# Charging.net
KiCad netlist of a schematic drawn in Altium Designer
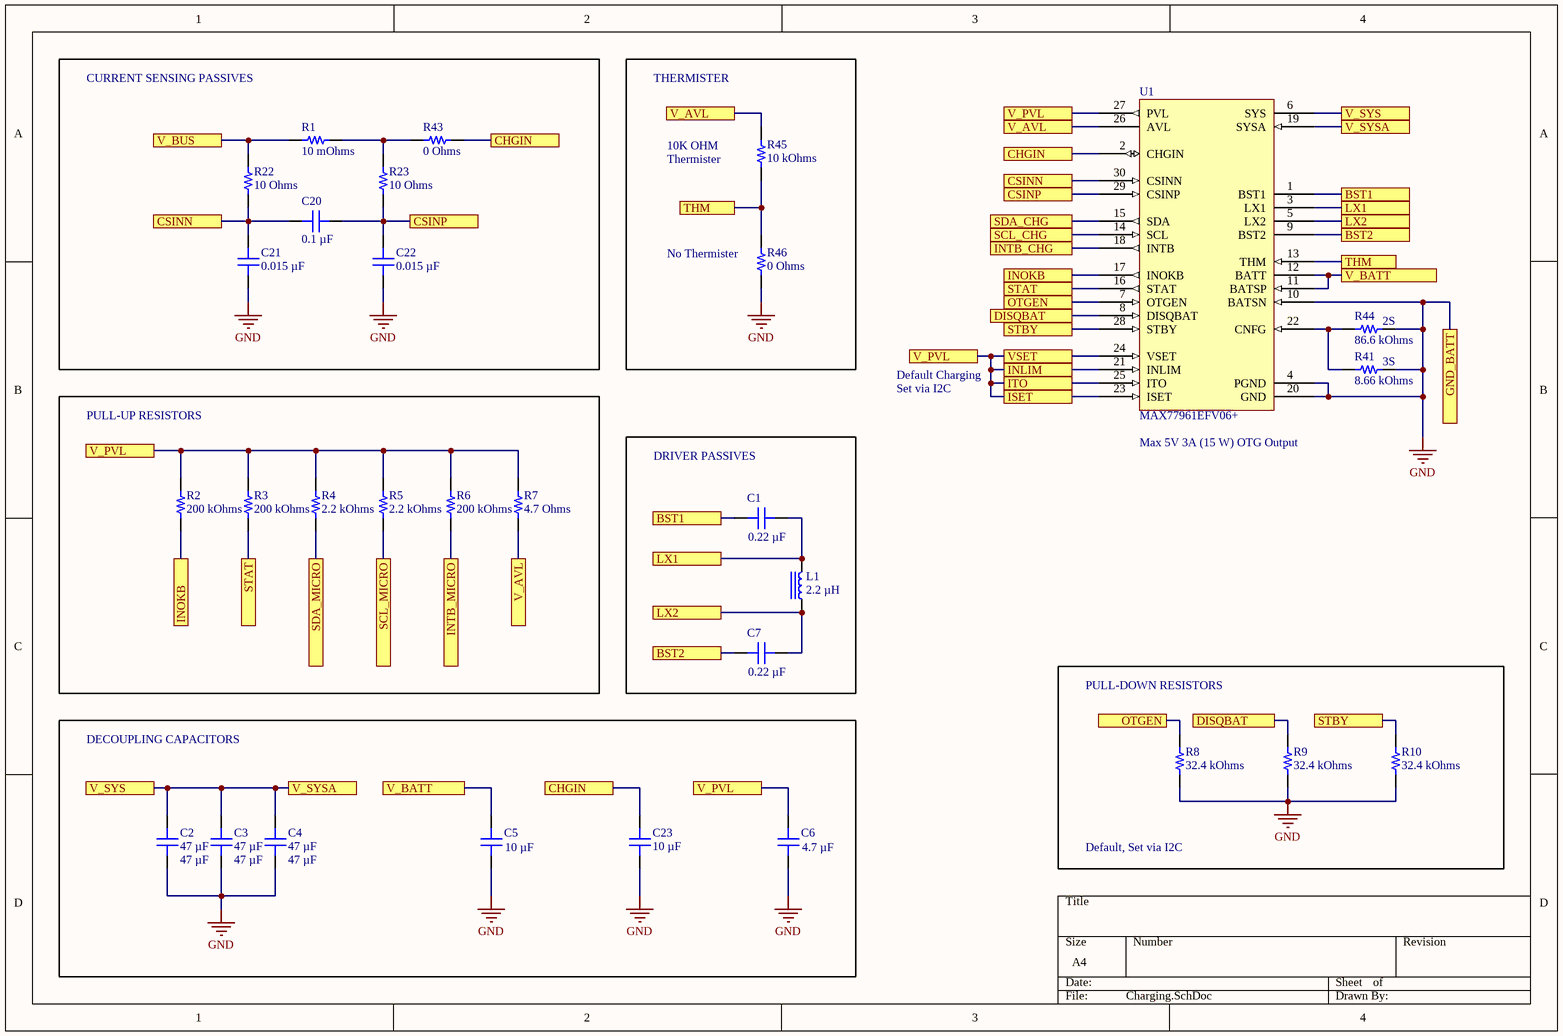
[diagram p0: Charging.SchDoc]

(export (version "E")
  (design (tool "Eeschema 10.0.6"))
  (components
    (comp (ref "C1")
      (value "0.22 µF")
      (footprint "CAP 0402_1005")
      (description "CAP CER 0.22UF 6.3V X7R 0402")
      (fields (field (name "PART NUMBER") "JMK105B7224KV-F") (field (name "MANUFACTURER") "Taiyo Yuden"))
      (libsource (lib "Celestial Altium Library - altium_library") (part "Capacitor"))
    )
    (comp (ref "C2")
      (value "47 µF")
      (footprint "CAP 1206_3216 - 0.8MM")
      (description "CAP CER 47UF 16V X5R 1206")
      (fields
        (field (name "PART NUMBER") "EMK316BBJ476ML-T")
        (field (name "ALTIUM_VALUE") "47 µF")
        (field (name "MANUFACTURER") "Taiyo Yuden")
      )
      (libsource (lib "Celestial Altium Library - altium_library") (part "Capacitor"))
    )
    (comp (ref "C3")
      (value "47 µF")
      (footprint "CAP 1206_3216 - 0.8MM")
      (description "CAP CER 47UF 16V X5R 1206")
      (fields
        (field (name "PART NUMBER") "EMK316BBJ476ML-T")
        (field (name "ALTIUM_VALUE") "47 µF")
        (field (name "MANUFACTURER") "Taiyo Yuden")
      )
      (libsource (lib "Celestial Altium Library - altium_library") (part "Capacitor"))
    )
    (comp (ref "C4")
      (value "47 µF")
      (footprint "CAP 1206_3216 - 0.8MM")
      (description "CAP CER 47UF 16V X5R 1206")
      (fields
        (field (name "PART NUMBER") "EMK316BBJ476ML-T")
        (field (name "ALTIUM_VALUE") "47 µF")
        (field (name "MANUFACTURER") "Taiyo Yuden")
      )
      (libsource (lib "Celestial Altium Library - altium_library") (part "Capacitor"))
    )
    (comp (ref "C5")
      (value "10 µF")
      (footprint "CAP 0603_1608")
      (description "CAP CER 10UF 16V X5R 0603")
      (fields
        (field (name "PART NUMBER") "GRT188R61C106ME13D")
        (field (name "MANUFACTURER") "Murata Electronics")
      )
      (libsource (lib "Celestial Altium Library - altium_library") (part "Capacitor"))
    )
    (comp (ref "C6")
      (value "4.7 µF")
      (footprint "CAP 0402_1005")
      (description "CAP CER 4.7UF 6.3V X5R 0402")
      (fields
        (field (name "PART NUMBER") "GRM155R60J475ME47D")
        (field (name "MANUFACTURER") "Murata Electronics")
      )
      (libsource (lib "Celestial Altium Library - altium_library") (part "Capacitor"))
    )
    (comp (ref "C7")
      (value "0.22 µF")
      (footprint "CAP 0402_1005")
      (description "CAP CER 0.22UF 6.3V X7R 0402")
      (fields (field (name "PART NUMBER") "JMK105B7224KV-F") (field (name "MANUFACTURER") "Taiyo Yuden"))
      (libsource (lib "Celestial Altium Library - altium_library") (part "Capacitor"))
    )
    (comp (ref "C20")
      (value "0.1 µF")
      (footprint "CAP 0402_1005")
      (description "CAP CER 0.1UF 10V X5R 0402")
      (fields
        (field (name "PART NUMBER") "CGA2B2X5R1A104M050BA")
        (field (name "MANUFACTURER") "TDK Corporation")
      )
      (libsource (lib "Celestial Altium Library - altium_library") (part "Capacitor"))
    )
    (comp (ref "C21")
      (value "0.015 µF")
      (footprint "CAP 0402_1005")
      (description "CAP CER 0.015UF 50V X7R 0402")
      (fields
        (field (name "PART NUMBER") "CGA2B3X7R1H153K050BB")
        (field (name "MANUFACTURER") "TDK Corporation")
      )
      (libsource (lib "Celestial Altium Library - altium_library") (part "Capacitor"))
    )
    (comp (ref "C22")
      (value "0.015 µF")
      (footprint "CAP 0402_1005")
      (description "CAP CER 0.015UF 50V X7R 0402")
      (fields
        (field (name "PART NUMBER") "CGA2B3X7R1H153K050BB")
        (field (name "MANUFACTURER") "TDK Corporation")
      )
      (libsource (lib "Celestial Altium Library - altium_library") (part "Capacitor"))
    )
    (comp (ref "C23")
      (value "10 µF")
      (footprint "CAP 1206_3216 - 0.8MM")
      (description "CAP CER 10UF 35V X7R 1206")
      (fields (field (name "PART NUMBER") "GMK316AB7106ML-TR") (field (name "MANUFACTURER") "Taiyo Yuden"))
      (libsource (lib "Celestial Altium Library - altium_library") (part "Capacitor"))
    )
    (comp (ref "L1")
      (value "2.2 µH")
      (footprint "TAIYO YUDEN NRS8030")
      (description "FIXED IND 2.2UH 4.8A 19.5MOHM SM")
      (fields (field (name "PART NUMBER") "NRS8030T2R2NJGJV") (field (name "MANUFACTURER") "Taiyo Yuden"))
      (libsource (lib "Celestial Altium Library - altium_library") (part "Inductor"))
    )
    (comp (ref "R1")
      (value "10 mOhms")
      (footprint "RES 2512_6432")
      (description "RES 0.01 OHM 1% 3W 2512")
      (fields (field (name "PART NUMBER") "WSLP2512R0100FEA") (field (name "MANUFACTURER") "Vishay Dale"))
      (libsource (lib "Celestial Altium Library - altium_library") (part "Resistor"))
    )
    (comp (ref "R2")
      (value "200 kOhms")
      (footprint "RES 0402_1005")
      (description "RES 200K OHM 0.1% 1/10W 0402")
      (fields
        (field (name "PART NUMBER") "RP73PF1E200KBTD")
        (field (name "MANUFACTURER") "TE Connectivity Passive Product")
      )
      (libsource (lib "Celestial Altium Library - altium_library") (part "Resistor"))
    )
    (comp (ref "R3")
      (value "200 kOhms")
      (footprint "RES 0402_1005")
      (description "RES 200K OHM 0.1% 1/10W 0402")
      (fields
        (field (name "PART NUMBER") "RP73PF1E200KBTD")
        (field (name "MANUFACTURER") "TE Connectivity Passive Product")
      )
      (libsource (lib "Celestial Altium Library - altium_library") (part "Resistor"))
    )
    (comp (ref "R4")
      (value "2.2 kOhms")
      (footprint "RES 0402_1005")
      (description "RES 2.2K OHM 0.1% 1/10W 0402")
      (fields (field (name "PART NUMBER") "TNPW04022K20BYEP") (field (name "MANUFACTURER") "Vishay Dale"))
      (libsource (lib "Celestial Altium Library - altium_library") (part "Resistor"))
    )
    (comp (ref "R5")
      (value "2.2 kOhms")
      (footprint "RES 0402_1005")
      (description "RES 2.2K OHM 0.1% 1/10W 0402")
      (fields (field (name "PART NUMBER") "TNPW04022K20BYEP") (field (name "MANUFACTURER") "Vishay Dale"))
      (libsource (lib "Celestial Altium Library - altium_library") (part "Resistor"))
    )
    (comp (ref "R6")
      (value "200 kOhms")
      (footprint "RES 0402_1005")
      (description "RES 200K OHM 0.1% 1/10W 0402")
      (fields
        (field (name "PART NUMBER") "RP73PF1E200KBTD")
        (field (name "MANUFACTURER") "TE Connectivity Passive Product")
      )
      (libsource (lib "Celestial Altium Library - altium_library") (part "Resistor"))
    )
    (comp (ref "R7")
      (value "4.7 Ohms")
      (footprint "RES 0402_1005")
      (description "RES SMD 4.7 OHM 5% 1/16W 0402")
      (fields (field (name "PART NUMBER") "CRCW04024R70JNED") (field (name "MANUFACTURER") "Vishay Dale"))
      (libsource (lib "Celestial Altium Library - altium_library") (part "Resistor"))
    )
    (comp (ref "R8")
      (value "32.4 kOhms")
      (footprint "RES 0402_1005")
      (description "RES SMD 32.4KOHM 0.1% 1/16W 0402")
      (fields
        (field (name "PART NUMBER") "CPF0402B32K4E1")
        (field (name "MANUFACTURER") "TE Connectivity Passive Product")
      )
      (libsource (lib "Celestial Altium Library - altium_library") (part "Resistor"))
    )
    (comp (ref "R9")
      (value "32.4 kOhms")
      (footprint "RES 0402_1005")
      (description "RES SMD 32.4KOHM 0.1% 1/16W 0402")
      (fields
        (field (name "PART NUMBER") "CPF0402B32K4E1")
        (field (name "MANUFACTURER") "TE Connectivity Passive Product")
      )
      (libsource (lib "Celestial Altium Library - altium_library") (part "Resistor"))
    )
    (comp (ref "R10")
      (value "32.4 kOhms")
      (footprint "RES 0402_1005")
      (description "RES SMD 32.4KOHM 0.1% 1/16W 0402")
      (fields
        (field (name "PART NUMBER") "CPF0402B32K4E1")
        (field (name "MANUFACTURER") "TE Connectivity Passive Product")
      )
      (libsource (lib "Celestial Altium Library - altium_library") (part "Resistor"))
    )
    (comp (ref "R22")
      (value "10 Ohms")
      (footprint "RES 0402_1005")
      (description "RES SMD 10 OHM 1% 1/16W 0402")
      (fields (field (name "PART NUMBER") "AC0402FR-0710RL") (field (name "MANUFACTURER") "Yageo"))
      (libsource (lib "Celestial Altium Library - altium_library") (part "Resistor"))
    )
    (comp (ref "R23")
      (value "10 Ohms")
      (footprint "RES 0402_1005")
      (description "RES SMD 10 OHM 1% 1/16W 0402")
      (fields (field (name "PART NUMBER") "AC0402FR-0710RL") (field (name "MANUFACTURER") "Yageo"))
      (libsource (lib "Celestial Altium Library - altium_library") (part "Resistor"))
    )
    (comp (ref "R41")
      (value "8.66 kOhms")
      (footprint "RES 0402_1005")
      (description "RES 8.66K OHM 1% 1/10W 0402")
      (fields
        (field (name "PART NUMBER") "RK73H1ETTP8661F")
        (field (name "MANUFACTURER") "KOA Speer Electronics, Inc.")
      )
      (libsource (lib "Celestial Altium Library - altium_library") (part "Resistor"))
    )
    (comp (ref "R43")
      (value "0 Ohms")
      (footprint "RES 1210_3225")
      (description "RES 0 OHM JUMPER 1/2W 1210")
      (fields (field (name "PART NUMBER") "RC1210JR-070RL") (field (name "MANUFACTURER") "Yageo"))
      (libsource (lib "Celestial Altium Library - altium_library") (part "Resistor"))
    )
    (comp (ref "R44")
      (value "86.6 kOhms")
      (footprint "RES 0402_1005")
      (description "RES 86.6K OHM 1% 1/16W 0402")
      (fields
        (field (name "PART NUMBER") "RMCF0402FT86K6")
        (field (name "MANUFACTURER") "Stackpole Electronics Inc")
      )
      (libsource (lib "Celestial Altium Library - altium_library") (part "Resistor"))
    )
    (comp (ref "R45")
      (value "10 kOhms")
      (footprint "RES 0603_1608")
      (description "RES SMD 10K OHM 5% 1/4W 0603")
      (fields (field (name "PART NUMBER") "RCS060310K0JNEA") (field (name "MANUFACTURER") "Vishay Dale"))
      (libsource (lib "Celestial Altium Library - altium_library") (part "Resistor"))
    )
    (comp (ref "R46")
      (value "0 Ohms")
      (footprint "RES 0603_1608")
      (description "RES SMD 0 OHM JUMPER 1/10W 0603")
      (fields (field (name "PART NUMBER") "RCA06030000ZSEA") (field (name "MANUFACTURER") "Vishay Dale"))
      (libsource (lib "Celestial Altium Library - altium_library") (part "Resistor"))
    )
    (comp (ref "U1")
      (value "MAX77961EFV06+")
      (footprint "FC2QFN 30L")
      (libsource (lib "Schlib2") (part "MAX77961EFV06+"))
    )
  )
  (nets
    (net (code "1") (name "/BST1") (class "Default")
      (node (ref "C1") (pin "1") (pinfunction "1_1") (pintype "passive"))
      (node (ref "U1") (pin "1") (pinfunction "BST1_1") (pintype "passive"))
    )
    (net (code "2") (name "/BST2") (class "Default")
      (node (ref "C7") (pin "1") (pinfunction "1_1") (pintype "passive"))
      (node (ref "U1") (pin "9") (pinfunction "BST2_9") (pintype "passive"))
    )
    (net (code "3") (name "/CHGIN") (class "Default")
      (node (ref "C23") (pin "2") (pinfunction "2_2") (pintype "passive"))
      (node (ref "R43") (pin "2") (pinfunction "2_2") (pintype "passive"))
      (node (ref "U1") (pin "2") (pinfunction "CHGIN_2") (pintype "bidirectional"))
    )
    (net (code "4") (name "/CSINN") (class "Default")
      (node (ref "C20") (pin "1") (pinfunction "1_1") (pintype "passive"))
      (node (ref "C21") (pin "2") (pinfunction "2_2") (pintype "passive"))
      (node (ref "R22") (pin "1") (pinfunction "1_1") (pintype "passive"))
      (node (ref "U1") (pin "30") (pinfunction "CSINN_30") (pintype "input"))
    )
    (net (code "5") (name "/CSINP") (class "Default")
      (node (ref "C20") (pin "2") (pinfunction "2_2") (pintype "passive"))
      (node (ref "C22") (pin "2") (pinfunction "2_2") (pintype "passive"))
      (node (ref "R23") (pin "1") (pinfunction "1_1") (pintype "passive"))
      (node (ref "U1") (pin "29") (pinfunction "CSINP_29") (pintype "input"))
    )
    (net (code "6") (name "/DISQBAT") (class "Default")
      (node (ref "R9") (pin "2") (pinfunction "2_2") (pintype "passive"))
      (node (ref "U1") (pin "8") (pinfunction "DISQBAT_8") (pintype "input"))
    )
    (net (code "7") (name "/INLIM") (class "Default")
      (node (ref "C6") (pin "2") (pinfunction "2_2") (pintype "passive"))
      (node (ref "R2") (pin "2") (pinfunction "2_2") (pintype "passive"))
      (node (ref "R3") (pin "2") (pinfunction "2_2") (pintype "passive"))
      (node (ref "R4") (pin "1") (pinfunction "1_1") (pintype "passive"))
      (node (ref "R5") (pin "1") (pinfunction "1_1") (pintype "passive"))
      (node (ref "R6") (pin "2") (pinfunction "2_2") (pintype "passive"))
      (node (ref "R7") (pin "2") (pinfunction "2_2") (pintype "passive"))
      (node (ref "U1") (pin "21") (pinfunction "INLIM_21") (pintype "input"))
      (node (ref "U1") (pin "23") (pinfunction "ISET_23") (pintype "input"))
      (node (ref "U1") (pin "24") (pinfunction "VSET_24") (pintype "input"))
      (node (ref "U1") (pin "25") (pinfunction "ITO_25") (pintype "input"))
      (node (ref "U1") (pin "27") (pinfunction "PVL_27") (pintype "output"))
    )
    (net (code "8") (name "/INOKB") (class "Default")
      (node (ref "R2") (pin "1") (pinfunction "1_1") (pintype "passive"))
      (node (ref "U1") (pin "17") (pinfunction "INOKB_17") (pintype "output"))
    )
    (net (code "9") (name "/INTB_CHG") (class "Default")
      (node (ref "U1") (pin "18") (pinfunction "INTB_18") (pintype "output"))
    )
    (net (code "10") (name "/INTB_MICRO") (class "Default")
      (node (ref "R6") (pin "1") (pinfunction "1_1") (pintype "passive"))
    )
    (net (code "11") (name "/LX1") (class "Default")
      (node (ref "C1") (pin "2") (pinfunction "2_2") (pintype "passive"))
      (node (ref "L1") (pin "2") (pinfunction "2_2") (pintype "passive"))
      (node (ref "U1") (pin "3") (pinfunction "LX1_3") (pintype "passive"))
    )
    (net (code "12") (name "/LX2") (class "Default")
      (node (ref "C7") (pin "2") (pinfunction "2_2") (pintype "passive"))
      (node (ref "L1") (pin "1") (pinfunction "1_1") (pintype "passive"))
      (node (ref "U1") (pin "5") (pinfunction "LX2_5") (pintype "passive"))
    )
    (net (code "13") (name "/OTGEN") (class "Default")
      (node (ref "R8") (pin "2") (pinfunction "2_2") (pintype "passive"))
      (node (ref "U1") (pin "7") (pinfunction "OTGEN_7") (pintype "input"))
    )
    (net (code "14") (name "/SCL_CHG") (class "Default")
      (node (ref "U1") (pin "14") (pinfunction "SCL_14") (pintype "input"))
    )
    (net (code "15") (name "/SCL_MICRO") (class "Default")
      (node (ref "R5") (pin "2") (pinfunction "2_2") (pintype "passive"))
    )
    (net (code "16") (name "/SDA_CHG") (class "Default")
      (node (ref "U1") (pin "15") (pinfunction "SDA_15") (pintype "output"))
    )
    (net (code "17") (name "/SDA_MICRO") (class "Default")
      (node (ref "R4") (pin "2") (pinfunction "2_2") (pintype "passive"))
    )
    (net (code "18") (name "/STAT") (class "Default")
      (node (ref "R3") (pin "1") (pinfunction "1_1") (pintype "passive"))
      (node (ref "U1") (pin "16") (pinfunction "STAT_16") (pintype "output"))
    )
    (net (code "19") (name "/STBY") (class "Default")
      (node (ref "R10") (pin "2") (pinfunction "2_2") (pintype "passive"))
      (node (ref "U1") (pin "28") (pinfunction "STBY_28") (pintype "input"))
    )
    (net (code "20") (name "/THM") (class "Default")
      (node (ref "R45") (pin "1") (pinfunction "1_1") (pintype "passive"))
      (node (ref "R46") (pin "2") (pinfunction "2_2") (pintype "passive"))
      (node (ref "U1") (pin "13") (pinfunction "THM_13") (pintype "input"))
    )
    (net (code "21") (name "/V_AVL") (class "Default")
      (node (ref "R45") (pin "2") (pinfunction "2_2") (pintype "passive"))
      (node (ref "R7") (pin "1") (pinfunction "1_1") (pintype "passive"))
      (node (ref "U1") (pin "26") (pinfunction "AVL_26") (pintype "passive"))
    )
    (net (code "22") (name "/V_BATT") (class "Default")
      (node (ref "C5") (pin "2") (pinfunction "2_2") (pintype "passive"))
      (node (ref "U1") (pin "11") (pinfunction "BATSP_11") (pintype "input"))
      (node (ref "U1") (pin "12") (pinfunction "BATT_12") (pintype "passive"))
    )
    (net (code "23") (name "/V_BUS") (class "Default")
      (node (ref "R1") (pin "1") (pinfunction "1_1") (pintype "passive"))
      (node (ref "R22") (pin "2") (pinfunction "2_2") (pintype "passive"))
    )
    (net (code "24") (name "/V_SYS") (class "Default")
      (node (ref "C2") (pin "2") (pinfunction "2_2") (pintype "passive"))
      (node (ref "C3") (pin "2") (pinfunction "2_2") (pintype "passive"))
      (node (ref "C4") (pin "2") (pinfunction "2_2") (pintype "passive"))
      (node (ref "U1") (pin "19") (pinfunction "SYSA_19") (pintype "input"))
      (node (ref "U1") (pin "6") (pinfunction "SYS_6") (pintype "passive"))
    )
    (net (code "25") (name "GND") (class "Default")
      (node (ref "C2") (pin "1") (pinfunction "1_1") (pintype "passive"))
      (node (ref "C21") (pin "1") (pinfunction "1_1") (pintype "passive"))
      (node (ref "C22") (pin "1") (pinfunction "1_1") (pintype "passive"))
      (node (ref "C23") (pin "1") (pinfunction "1_1") (pintype "passive"))
      (node (ref "C3") (pin "1") (pinfunction "1_1") (pintype "passive"))
      (node (ref "C4") (pin "1") (pinfunction "1_1") (pintype "passive"))
      (node (ref "C5") (pin "1") (pinfunction "1_1") (pintype "passive"))
      (node (ref "C6") (pin "1") (pinfunction "1_1") (pintype "passive"))
      (node (ref "R10") (pin "1") (pinfunction "1_1") (pintype "passive"))
      (node (ref "R41") (pin "2") (pinfunction "2_2") (pintype "passive"))
      (node (ref "R44") (pin "2") (pinfunction "2_2") (pintype "passive"))
      (node (ref "R46") (pin "1") (pinfunction "1_1") (pintype "passive"))
      (node (ref "R8") (pin "1") (pinfunction "1_1") (pintype "passive"))
      (node (ref "R9") (pin "1") (pinfunction "1_1") (pintype "passive"))
      (node (ref "U1") (pin "10") (pinfunction "BATSN_10") (pintype "input"))
      (node (ref "U1") (pin "20") (pinfunction "GND_20") (pintype "passive"))
      (node (ref "U1") (pin "4") (pinfunction "PGND_4") (pintype "passive"))
    )
    (net (code "26") (name "Net-(R1-Pad2)") (class "Default")
      (node (ref "R1") (pin "2") (pinfunction "2_2") (pintype "passive"))
      (node (ref "R23") (pin "2") (pinfunction "2_2") (pintype "passive"))
      (node (ref "R43") (pin "1") (pinfunction "1_1") (pintype "passive"))
    )
    (net (code "27") (name "Net-(U1-CNFG)") (class "Default")
      (node (ref "R41") (pin "1") (pinfunction "1_1") (pintype "passive"))
      (node (ref "R44") (pin "1") (pinfunction "1_1") (pintype "passive"))
      (node (ref "U1") (pin "22") (pinfunction "CNFG_22") (pintype "input"))
    )
  )
)
